# TXMIX-SE.net
KiCad netlist of a schematic drawn in Altium Designer
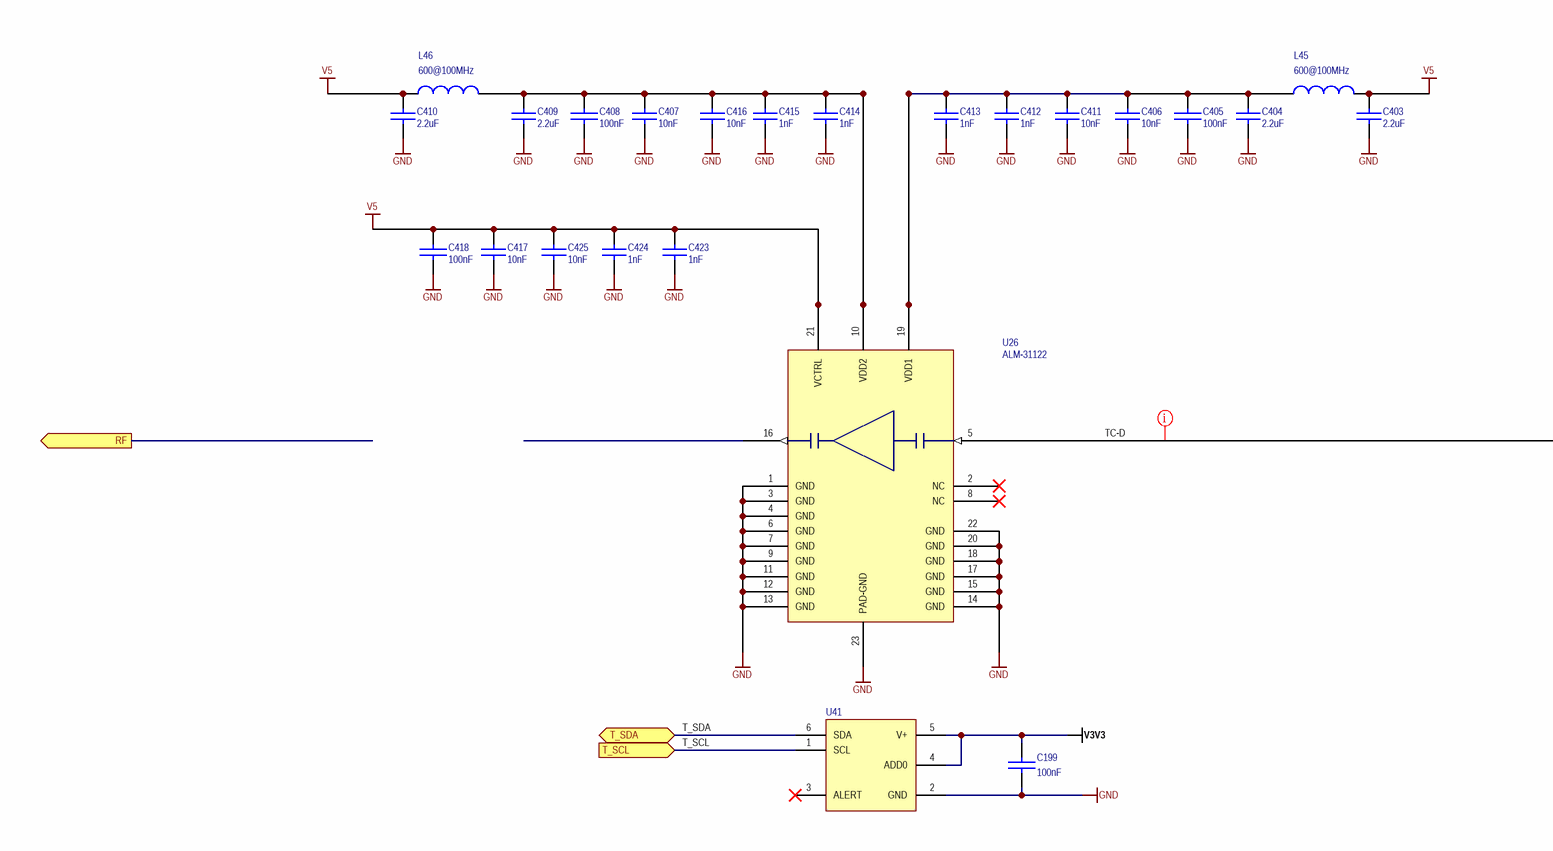
[diagram p0: TXMIX-SE.SchDoc, left]
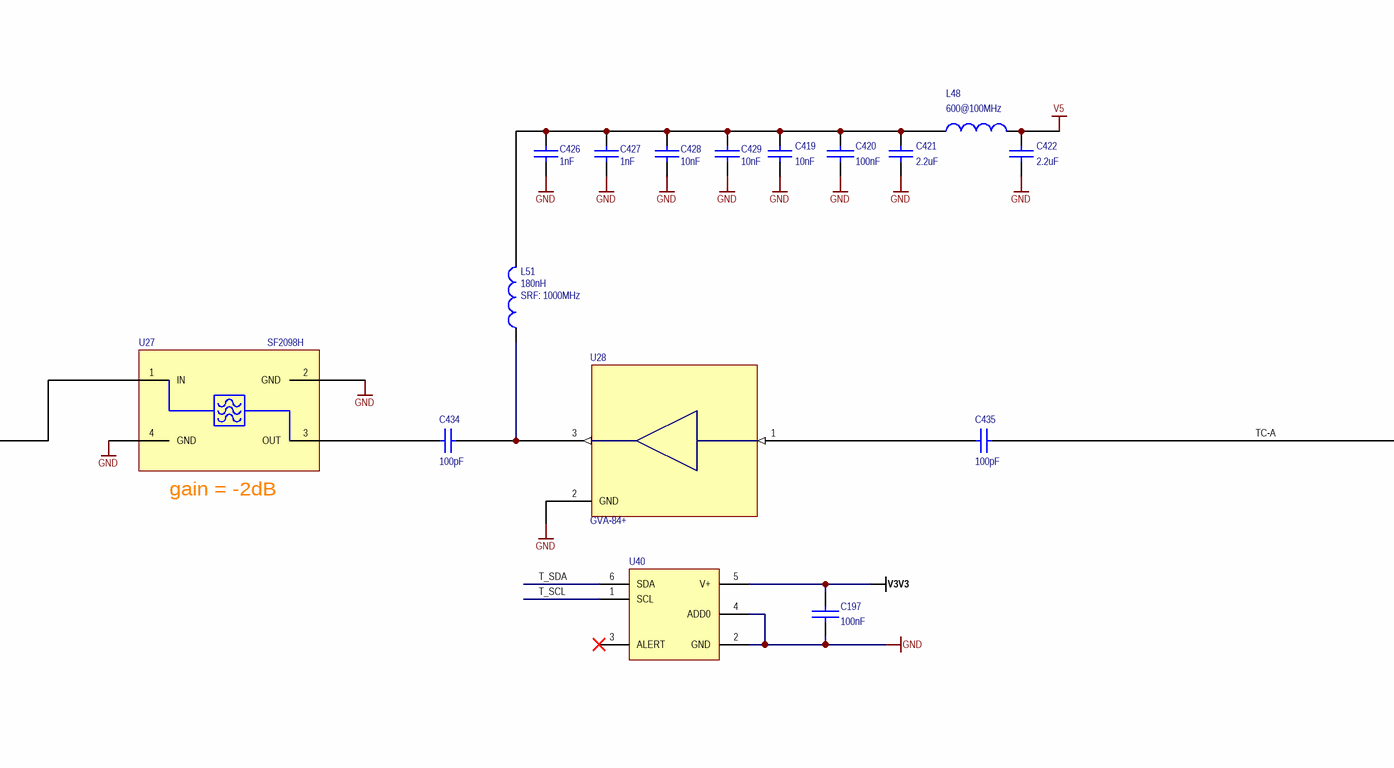
[diagram p1: TXMIX-SE.SchDoc, middle]
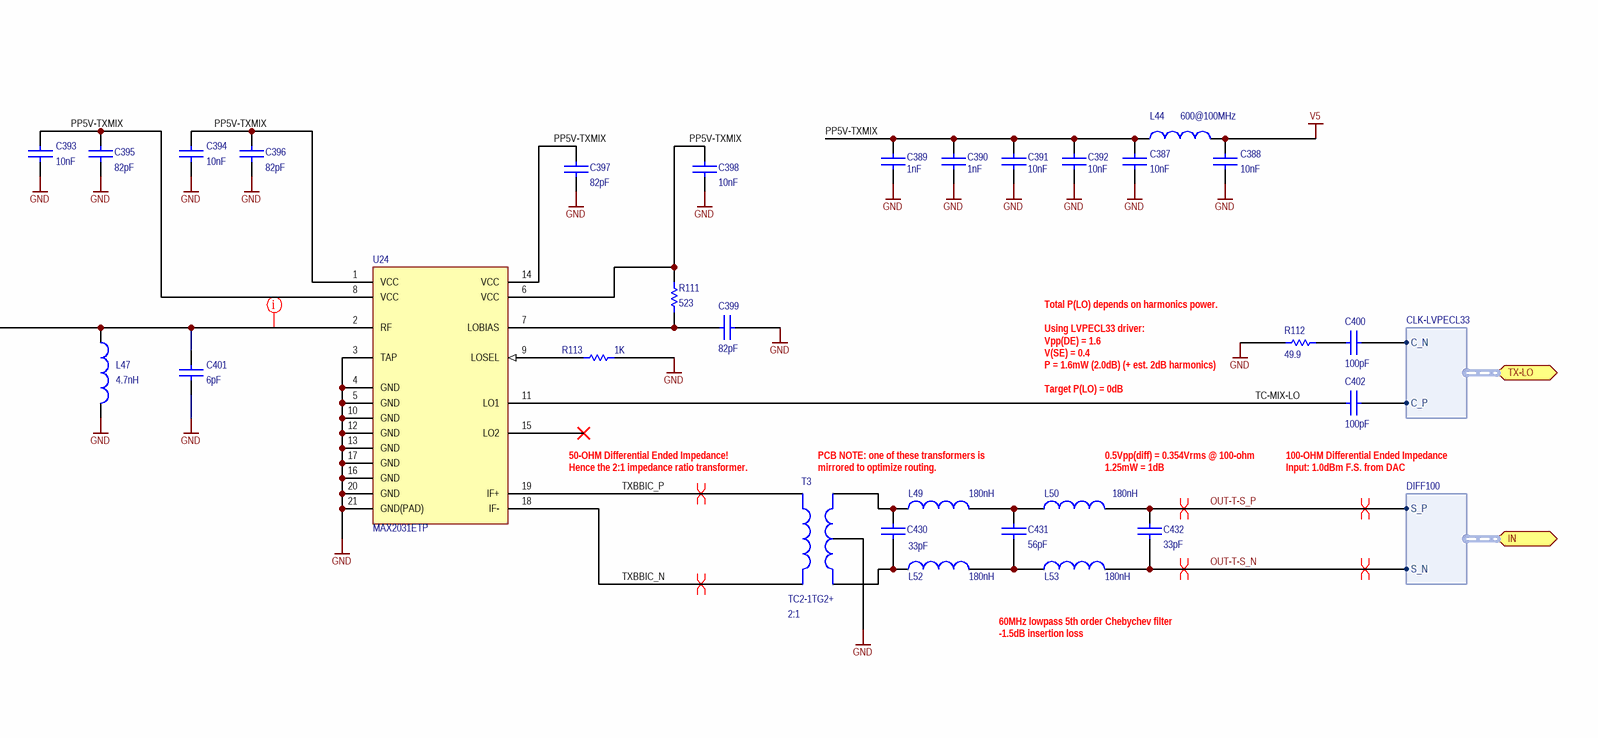
[diagram p2: TXMIX-SE.SchDoc, right]

(export (version "E")
  (design (tool "Eeschema 10.0.6"))
  (components
    (comp (ref "C197")
      (value "100nF")
      (footprint "CAPC100X50X55L25N")
      (description "Ceramic Capacitor 100nF ±10% 16V X7R 0402")
      (fields (field (name "MANUFACTURER") "Murata") (field (name "VOLTAGE") "16V"))
      (libsource (lib "*") (part "CAP"))
    )
    (comp (ref "C199")
      (value "100nF")
      (footprint "CAPC100X50X55L25N")
      (description "Ceramic Capacitor 100nF ±10% 16V X7R 0402")
      (fields (field (name "MANUFACTURER") "Murata") (field (name "VOLTAGE") "16V"))
      (libsource (lib "*") (part "CAP"))
    )
    (comp (ref "C387")
      (value "10nF")
      (footprint "CAPC100X50X55L25N")
      (description "Ceramic Capacitor 10nF ±10% 50V X7R 0402")
      (fields (field (name "VOLTAGE") "50V") (field (name "MANUFACTURER") "Murata"))
      (libsource (lib "Graviton") (part "CAP 0402"))
    )
    (comp (ref "C388")
      (value "10nF")
      (footprint "CAPC100X50X55L25N")
      (description "Ceramic Capacitor 10nF ±10% 50V X7R 0402")
      (fields (field (name "VOLTAGE") "50V") (field (name "MANUFACTURER") "Murata"))
      (libsource (lib "Graviton") (part "CAP 0402"))
    )
    (comp (ref "C389")
      (value "1nF")
      (footprint "CAPC100X50X55L25N")
      (description "Ceramic Capacitor 1nF ±10% 50V X7R 0402")
      (fields (field (name "VOLTAGE") "50V") (field (name "MANUFACTURER") "Murata"))
      (libsource (lib "Graviton") (part "CAP 0402"))
    )
    (comp (ref "C390")
      (value "1nF")
      (footprint "CAPC100X50X55L25N")
      (description "Ceramic Capacitor 1nF ±10% 50V X7R 0402")
      (fields (field (name "VOLTAGE") "50V") (field (name "MANUFACTURER") "Murata"))
      (libsource (lib "Graviton") (part "CAP 0402"))
    )
    (comp (ref "C391")
      (value "10nF")
      (footprint "CAPC100X50X55L25N")
      (description "Ceramic Capacitor 10nF ±10% 50V X7R 0402")
      (fields (field (name "VOLTAGE") "50V") (field (name "MANUFACTURER") "Murata"))
      (libsource (lib "Graviton") (part "CAP 0402"))
    )
    (comp (ref "C392")
      (value "10nF")
      (footprint "CAPC100X50X55L25N")
      (description "Ceramic Capacitor 10nF ±10% 50V X7R 0402")
      (fields (field (name "VOLTAGE") "50V") (field (name "MANUFACTURER") "Murata"))
      (libsource (lib "Graviton") (part "CAP 0402"))
    )
    (comp (ref "C393")
      (value "10nF")
      (footprint "CAPC100X50X55L25N")
      (description "Ceramic Capacitor 10nF ±10% 50V X7R 0402")
      (fields (field (name "VOLTAGE") "50V") (field (name "MANUFACTURER") "Murata"))
      (libsource (lib "Graviton") (part "CAP 0402"))
    )
    (comp (ref "C394")
      (value "10nF")
      (footprint "CAPC100X50X55L25N")
      (description "Ceramic Capacitor 10nF ±10% 50V X7R 0402")
      (fields (field (name "VOLTAGE") "50V") (field (name "MANUFACTURER") "Murata"))
      (libsource (lib "Graviton") (part "CAP 0402"))
    )
    (comp (ref "C395")
      (value "82pF")
      (footprint "CAPC100X50X55L25N")
      (description "Ceramic Capacitor 82pF ±5% 25V NP0 0402")
      (fields (field (name "VOLTAGE") "25V") (field (name "MANUFACTURER") "Vishay Vitramon"))
      (libsource (lib "generic") (part "CAP"))
    )
    (comp (ref "C396")
      (value "82pF")
      (footprint "CAPC100X50X55L25N")
      (description "Ceramic Capacitor 82pF ±5% 25V NP0 0402")
      (fields (field (name "MANUFACTURER") "Vishay Vitramon") (field (name "VOLTAGE") "25V"))
      (libsource (lib "generic") (part "CAP"))
    )
    (comp (ref "C397")
      (value "82pF")
      (footprint "CAPC100X50X55L25N")
      (description "Ceramic Capacitor 82pF ±5% 25V NP0 0402")
      (fields (field (name "VOLTAGE") "25V") (field (name "MANUFACTURER") "Vishay Vitramon"))
      (libsource (lib "generic") (part "CAP"))
    )
    (comp (ref "C398")
      (value "10nF")
      (footprint "CAPC100X50X55L25N")
      (description "Ceramic Capacitor 10nF ±10% 50V X7R 0402")
      (fields (field (name "VOLTAGE") "50V") (field (name "MANUFACTURER") "Murata"))
      (libsource (lib "Graviton") (part "CAP 0402"))
    )
    (comp (ref "C399")
      (value "82pF")
      (footprint "CAPC100X50X55L25N")
      (description "Ceramic Capacitor 82pF ±5% 25V NP0 0402")
      (fields (field (name "VOLTAGE") "25V") (field (name "MANUFACTURER") "Vishay Vitramon"))
      (libsource (lib "generic") (part "CAP"))
    )
    (comp (ref "C400")
      (value "100pF")
      (footprint "CAPC100X50X55L25N")
      (description "Ceramic Capacitor 100pF ±1% 25V NP0 0402")
      (fields (field (name "VOLTAGE") "25V") (field (name "MANUFACTURER") "Kemet"))
      (libsource (lib "generic") (part "CAP 0603"))
    )
    (comp (ref "C401")
      (value "6pF")
      (footprint "CAPC100X50X55L25N")
      (description "Ceramic Capacitor 6pF ±0.25pF 50V NP0 RF 0402")
      (fields (field (name "VOLTAGE") "50V") (field (name "MANUFACTURER") "Murata"))
      (libsource (lib "generic") (part "CAP 0402"))
    )
    (comp (ref "C402")
      (value "100pF")
      (footprint "CAPC100X50X55L25N")
      (description "Ceramic Capacitor 100pF ±1% 25V NP0 0402")
      (fields (field (name "VOLTAGE") "25V") (field (name "MANUFACTURER") "Kemet"))
      (libsource (lib "generic") (part "CAP 0603"))
    )
    (comp (ref "C403")
      (value "2.2uF")
      (footprint "generic:0805")
      (description "Ceramic Capacitor 2.2uF ±10% 10V X7R 0603")
      (fields (field (name "VOLTAGE") "10V") (field (name "MANUFACTURER") "Murata"))
      (libsource (lib "Graviton") (part "CAP 0805"))
    )
    (comp (ref "C404")
      (value "2.2uF")
      (footprint "generic:0805")
      (description "Ceramic Capacitor 2.2uF ±10% 10V X7R 0603")
      (fields (field (name "VOLTAGE") "10V") (field (name "MANUFACTURER") "Murata"))
      (libsource (lib "Graviton") (part "CAP 0805"))
    )
    (comp (ref "C405")
      (value "100nF")
      (footprint "CAPC100X50X55L25N")
      (description "Ceramic Capacitor 100nF ±10% 16V X7R 0402")
      (fields (field (name "MANUFACTURER") "Murata") (field (name "VOLTAGE") "16V"))
      (libsource (lib "*") (part "CAP"))
    )
    (comp (ref "C406")
      (value "10nF")
      (footprint "CAPC100X50X55L25N")
      (description "Ceramic Capacitor 10nF ±10% 50V X7R 0402")
      (fields (field (name "VOLTAGE") "50V") (field (name "MANUFACTURER") "Murata"))
      (libsource (lib "Graviton") (part "CAP 0402"))
    )
    (comp (ref "C407")
      (value "10nF")
      (footprint "CAPC100X50X55L25N")
      (description "Ceramic Capacitor 10nF ±10% 50V X7R 0402")
      (fields (field (name "VOLTAGE") "50V") (field (name "MANUFACTURER") "Murata"))
      (libsource (lib "Graviton") (part "CAP 0402"))
    )
    (comp (ref "C408")
      (value "100nF")
      (footprint "CAPC100X50X55L25N")
      (description "Ceramic Capacitor 100nF ±10% 16V X7R 0402")
      (fields (field (name "MANUFACTURER") "Murata") (field (name "VOLTAGE") "16V"))
      (libsource (lib "*") (part "CAP"))
    )
    (comp (ref "C409")
      (value "2.2uF")
      (footprint "generic:0805")
      (description "Ceramic Capacitor 2.2uF ±10% 10V X7R 0603")
      (fields (field (name "VOLTAGE") "10V") (field (name "MANUFACTURER") "Murata"))
      (libsource (lib "Graviton") (part "CAP 0805"))
    )
    (comp (ref "C410")
      (value "2.2uF")
      (footprint "generic:0805")
      (description "Ceramic Capacitor 2.2uF ±10% 10V X7R 0603")
      (fields (field (name "VOLTAGE") "10V") (field (name "MANUFACTURER") "Murata"))
      (libsource (lib "Graviton") (part "CAP 0805"))
    )
    (comp (ref "C411")
      (value "10nF")
      (footprint "CAPC100X50X55L25N")
      (description "Ceramic Capacitor 10nF ±10% 50V X7R 0402")
      (fields (field (name "VOLTAGE") "50V") (field (name "MANUFACTURER") "Murata"))
      (libsource (lib "Graviton") (part "CAP 0402"))
    )
    (comp (ref "C412")
      (value "1nF")
      (footprint "CAPC100X50X55L25N")
      (description "Ceramic Capacitor 1nF ±10% 50V X7R 0402")
      (fields (field (name "VOLTAGE") "50V") (field (name "MANUFACTURER") "Murata"))
      (libsource (lib "Graviton") (part "CAP 0402"))
    )
    (comp (ref "C413")
      (value "1nF")
      (footprint "CAPC100X50X55L25N")
      (description "Ceramic Capacitor 1nF ±10% 50V X7R 0402")
      (fields (field (name "VOLTAGE") "50V") (field (name "MANUFACTURER") "Murata"))
      (libsource (lib "Graviton") (part "CAP 0402"))
    )
    (comp (ref "C414")
      (value "1nF")
      (footprint "CAPC100X50X55L25N")
      (description "Ceramic Capacitor 1nF ±10% 50V X7R 0402")
      (fields (field (name "VOLTAGE") "50V") (field (name "MANUFACTURER") "Murata"))
      (libsource (lib "Graviton") (part "CAP 0402"))
    )
    (comp (ref "C415")
      (value "1nF")
      (footprint "CAPC100X50X55L25N")
      (description "Ceramic Capacitor 1nF ±10% 50V X7R 0402")
      (fields (field (name "VOLTAGE") "50V") (field (name "MANUFACTURER") "Murata"))
      (libsource (lib "Graviton") (part "CAP 0402"))
    )
    (comp (ref "C416")
      (value "10nF")
      (footprint "CAPC100X50X55L25N")
      (description "Ceramic Capacitor 10nF ±10% 50V X7R 0402")
      (fields (field (name "VOLTAGE") "50V") (field (name "MANUFACTURER") "Murata"))
      (libsource (lib "Graviton") (part "CAP 0402"))
    )
    (comp (ref "C417")
      (value "10nF")
      (footprint "CAPC100X50X55L25N")
      (description "Ceramic Capacitor 10nF ±10% 50V X7R 0402")
      (fields (field (name "VOLTAGE") "50V") (field (name "MANUFACTURER") "Murata"))
      (libsource (lib "Graviton") (part "CAP 0402"))
    )
    (comp (ref "C418")
      (value "100nF")
      (footprint "CAPC100X50X55L25N")
      (description "Ceramic Capacitor 100nF ±10% 16V X7R 0402")
      (fields (field (name "MANUFACTURER") "Murata") (field (name "VOLTAGE") "16V"))
      (libsource (lib "*") (part "CAP"))
    )
    (comp (ref "C419")
      (value "10nF")
      (footprint "CAPC100X50X55L25N")
      (description "Ceramic Capacitor 10nF ±10% 50V X7R 0402")
      (fields (field (name "VOLTAGE") "50V") (field (name "MANUFACTURER") "Murata"))
      (libsource (lib "Graviton") (part "CAP 0402"))
    )
    (comp (ref "C420")
      (value "100nF")
      (footprint "CAPC100X50X55L25N")
      (description "Ceramic Capacitor 100nF ±10% 16V X7R 0402")
      (fields (field (name "MANUFACTURER") "Murata") (field (name "VOLTAGE") "16V"))
      (libsource (lib "*") (part "CAP"))
    )
    (comp (ref "C421")
      (value "2.2uF")
      (footprint "generic:0805")
      (description "Ceramic Capacitor 2.2uF ±10% 10V X7R 0603")
      (fields (field (name "VOLTAGE") "10V") (field (name "MANUFACTURER") "Murata"))
      (libsource (lib "Graviton") (part "CAP 0805"))
    )
    (comp (ref "C422")
      (value "2.2uF")
      (footprint "generic:0805")
      (description "Ceramic Capacitor 2.2uF ±10% 10V X7R 0603")
      (fields (field (name "VOLTAGE") "10V") (field (name "MANUFACTURER") "Murata"))
      (libsource (lib "Graviton") (part "CAP 0805"))
    )
    (comp (ref "C423")
      (value "1nF")
      (footprint "CAPC100X50X55L25N")
      (description "Ceramic Capacitor 1nF ±10% 50V X7R 0402")
      (fields (field (name "VOLTAGE") "50V") (field (name "MANUFACTURER") "Murata"))
      (libsource (lib "Graviton") (part "CAP 0402"))
    )
    (comp (ref "C424")
      (value "1nF")
      (footprint "CAPC100X50X55L25N")
      (description "Ceramic Capacitor 1nF ±10% 50V X7R 0402")
      (fields (field (name "VOLTAGE") "50V") (field (name "MANUFACTURER") "Murata"))
      (libsource (lib "Graviton") (part "CAP 0402"))
    )
    (comp (ref "C425")
      (value "10nF")
      (footprint "CAPC100X50X55L25N")
      (description "Ceramic Capacitor 10nF ±10% 50V X7R 0402")
      (fields (field (name "VOLTAGE") "50V") (field (name "MANUFACTURER") "Murata"))
      (libsource (lib "Graviton") (part "CAP 0402"))
    )
    (comp (ref "C426")
      (value "1nF")
      (footprint "CAPC100X50X55L25N")
      (description "Ceramic Capacitor 1nF ±10% 50V X7R 0402")
      (fields (field (name "VOLTAGE") "50V") (field (name "MANUFACTURER") "Murata"))
      (libsource (lib "Graviton") (part "CAP 0402"))
    )
    (comp (ref "C427")
      (value "1nF")
      (footprint "CAPC100X50X55L25N")
      (description "Ceramic Capacitor 1nF ±10% 50V X7R 0402")
      (fields (field (name "VOLTAGE") "50V") (field (name "MANUFACTURER") "Murata"))
      (libsource (lib "Graviton") (part "CAP 0402"))
    )
    (comp (ref "C428")
      (value "10nF")
      (footprint "CAPC100X50X55L25N")
      (description "Ceramic Capacitor 10nF ±10% 50V X7R 0402")
      (fields (field (name "VOLTAGE") "50V") (field (name "MANUFACTURER") "Murata"))
      (libsource (lib "Graviton") (part "CAP 0402"))
    )
    (comp (ref "C429")
      (value "10nF")
      (footprint "CAPC100X50X55L25N")
      (description "Ceramic Capacitor 10nF ±10% 50V X7R 0402")
      (fields (field (name "VOLTAGE") "50V") (field (name "MANUFACTURER") "Murata"))
      (libsource (lib "Graviton") (part "CAP 0402"))
    )
    (comp (ref "C430")
      (value "33pF")
      (footprint "CAPC100X50X55L25N")
      (description "Ceramic Capacitor 33pF ±5% 50V NP0 0402")
      (fields (field (name "VOLTAGE") "50V") (field (name "MANUFACTURER") "Murata"))
      (libsource (lib "Graviton") (part "CAP 0402"))
    )
    (comp (ref "C431")
      (value "56pF")
      (footprint "CAPC100X50X55L25N")
      (description "Ceramic Capacitor 56pF ±5% 50V NP0 0402")
      (fields (field (name "VOLTAGE") "50V") (field (name "MANUFACTURER") "Murata"))
      (libsource (lib "Graviton") (part "CAP 0402"))
    )
    (comp (ref "C432")
      (value "33pF")
      (footprint "CAPC100X50X55L25N")
      (description "Ceramic Capacitor 33pF ±5% 50V NP0 0402")
      (fields (field (name "VOLTAGE") "50V") (field (name "MANUFACTURER") "Murata"))
      (libsource (lib "Graviton") (part "CAP 0402"))
    )
    (comp (ref "C434")
      (value "100pF")
      (footprint "CAPC100X50X55L25N")
      (description "Ceramic Capacitor 100pF ±1% 25V NP0 0402")
      (fields (field (name "MANUFACTURER") "Kemet") (field (name "VOLTAGE") "25V"))
      (libsource (lib "generic") (part "CAP 0603"))
    )
    (comp (ref "C435")
      (value "100pF")
      (footprint "CAPC100X50X55L25N")
      (description "Ceramic Capacitor 100pF ±1% 25V NP0 0402")
      (fields (field (name "VOLTAGE") "25V") (field (name "MANUFACTURER") "Kemet"))
      (libsource (lib "generic") (part "CAP 0603"))
    )
    (comp (ref "L44")
      (value "600@100MHz")
      (footprint "INDC1005X55N")
      (description "Ferrite Bead 600-Ohm @ 100MHz 900mA 0402")
      (fields (field (name "MANUFACTURER") "Murata") (field (name "TOLERANCE") "±25%"))
      (libsource (lib "") (part "IND 0402_1"))
    )
    (comp (ref "L45")
      (value "600@100MHz")
      (footprint "INDC1005X55N")
      (description "Ferrite Bead 600-Ohm @ 100MHz 900mA 0402")
      (fields (field (name "MANUFACTURER") "Murata") (field (name "TOLERANCE") "±25%"))
      (libsource (lib "Graviton") (part "IND 0402"))
    )
    (comp (ref "L46")
      (value "600@100MHz")
      (footprint "INDC1005X55N")
      (description "Ferrite Bead 600-Ohm @ 100MHz 900mA 0402")
      (fields (field (name "MANUFACTURER") "Murata") (field (name "TOLERANCE") "±25%"))
      (libsource (lib "Graviton") (part "IND 0402"))
    )
    (comp (ref "L47")
      (value "4.7nH")
      (footprint "0603")
      (description "Inductor Multilayer 4.7nH ±5% 0603")
      (fields (field (name "MANUFACTURER") "Murata") (field (name "TOLERANCE") "±0.3nH"))
      (libsource (lib "Graviton") (part "IND 0603"))
    )
    (comp (ref "L48")
      (value "600@100MHz")
      (footprint "INDC1005X55N")
      (description "Ferrite Bead 600-Ohm @ 100MHz 900mA 0402")
      (fields (field (name "MANUFACTURER") "Murata") (field (name "TOLERANCE") "±25%"))
      (libsource (lib "") (part "IND 0402_1"))
    )
    (comp (ref "L49")
      (value "180nH")
      (footprint "0603")
      (description "Inductor Wirewound 180nH ±2% 0603")
      (fields (field (name "MANUFACTURER") "Murata") (field (name "TOLERANCE") "±2%"))
      (libsource (lib "generic") (part "INDUCTOR"))
    )
    (comp (ref "L50")
      (value "180nH")
      (footprint "0603")
      (description "Inductor Wirewound 180nH ±2% 0603")
      (fields (field (name "MANUFACTURER") "Murata") (field (name "TOLERANCE") "±2%"))
      (libsource (lib "generic") (part "INDUCTOR"))
    )
    (comp (ref "L51")
      (value "180nH")
      (footprint "INDC1005X55N")
      (description "Wirewound Inductor 180nH 560mA 0402")
      (fields
        (field (name "MANUFACTURER") "Murata")
        (field (name "SRF") "1000MHz")
        (field (name "Comment") "LQW15CNR18J1ZD")
      )
      (libsource (lib "") (part "IND 0603_1"))
    )
    (comp (ref "L52")
      (value "180nH")
      (footprint "0603")
      (description "Inductor Wirewound 180nH ±2% 0603")
      (fields (field (name "MANUFACTURER") "Murata") (field (name "TOLERANCE") "±2%"))
      (libsource (lib "generic") (part "INDUCTOR"))
    )
    (comp (ref "L53")
      (value "180nH")
      (footprint "0603")
      (description "Inductor Wirewound 180nH ±2% 0603")
      (fields (field (name "MANUFACTURER") "Murata") (field (name "TOLERANCE") "±2%"))
      (libsource (lib "generic") (part "INDUCTOR"))
    )
    (comp (ref "R111")
      (value "523")
      (footprint "generic:0603")
      (description "Thick Film Resistor 523 ±1% 0603")
      (fields (field (name "MANUFACTURER") "Yageo") (field (name "TOLERANCE") "±1%"))
      (libsource (lib "generic") (part "RES 0603"))
    )
    (comp (ref "R112")
      (value "49.9")
      (footprint "generic:0603")
      (description "Thick Film Resistor 49.9 ±1% 0603")
      (fields (field (name "MANUFACTURER") "Panasonic") (field (name "TOLERANCE") "±1%"))
      (libsource (lib "generic") (part "RES 0603"))
    )
    (comp (ref "R113")
      (value "1K")
      (footprint "RESC1005X40N")
      (description "Thick Film Resistor 1k ±1% 0402")
      (fields (field (name "MANUFACTURER") "Yageo") (field (name "TOLERANCE") "±1%"))
      (libsource (lib "Graviton") (part "RES 0402"))
    )
    (comp (ref "T3")
      (value "2:1")
      (footprint "AT224-1A")
      (description "RF Transformer 0.4 to 500MHz SMD")
      (fields
        (field (name "MANUFACTURER P/N") "TC2-1TG2+")
        (field (name "MANUFACTURER") "Mini-Circuits")
        (field (name "Comment") "TC2-1TG2+")
      )
      (libsource (lib "phase4") (part "TC1-1TG2+"))
    )
    (comp (ref "U24")
      (value "MAX2031ETP")
      (footprint "QFN21P65_500X500X80L55X30T320N")
      (description "Upconversion/Downconversion Mixer")
      (fields (field (name "MANUFACTURER") "Maxim"))
      (libsource (lib "maxim") (part "MAX2031ETP"))
    )
    (comp (ref "U26")
      (value "ALM-31122")
      (footprint "ALM-31122")
      (description "1-watt High-Linearity Power Amplifier")
      (fields (field (name "MANUFACTURER") "Avago"))
      (libsource (lib "avago") (part "ALM-31122"))
    )
    (comp (ref "U27")
      (value "SF2098H")
      (footprint "rfm:SM2016-4")
      (description "915 MHz SAW Filter")
      (fields (field (name "MANUFACTURER") "RFM"))
      (libsource (lib "rfm") (part "SF2098H"))
    )
    (comp (ref "U28")
      (value "GVA-84+")
      (footprint "SOT89")
      (description "High Gain Monolithic Amplifier, DC-7GHz 24dB Gain")
      (fields (field (name "MANUFACTURER") "Mini-Circuits"))
      (libsource (lib "Mini-Circuits") (part "GVA-84+"))
    )
    (comp (ref "U40")
      (value "TMP116AIDRVT")
      (footprint "SON7P65_200X200X80L25X30T170X110N")
      (description "High-Accuracy Temperature Sensor")
      (fields (field (name "MANUFACTURER") "Texas Instruments"))
      (libsource (lib "ti") (part "TMP116AIDRV"))
    )
    (comp (ref "U41")
      (value "TMP116AIDRVT")
      (footprint "SON7P65_200X200X80L25X30T170X110N")
      (description "High-Accuracy Temperature Sensor")
      (fields (field (name "MANUFACTURER") "Texas Instruments"))
      (libsource (lib "ti") (part "TMP116AIDRV"))
    )
  )
  (nets
    (net (code "3") (name "/C_N") (class "Default")
      (node (ref "C400") (pin "2") (pinfunction "2_2") (pintype "passive"))
    )
    (net (code "4") (name "/C_P") (class "Default")
      (node (ref "C402") (pin "2") (pinfunction "2_2") (pintype "passive"))
    )
    (net (code "5") (name "/OUT-T-S_N") (class "Default")
      (node (ref "C432") (pin "1") (pinfunction "1_1") (pintype "passive"))
      (node (ref "L53") (pin "1") (pinfunction "1_1") (pintype "passive"))
    )
    (net (code "6") (name "/OUT-T-S_P") (class "Default")
      (node (ref "C432") (pin "2") (pinfunction "2_2") (pintype "passive"))
      (node (ref "L50") (pin "1") (pinfunction "1_1") (pintype "passive"))
    )
    (net (code "7") (name "/PP5V-TXMIX") (class "Default")
      (node (ref "C387") (pin "2") (pinfunction "2_2") (pintype "passive"))
      (node (ref "C389") (pin "2") (pinfunction "2_2") (pintype "passive"))
      (node (ref "C390") (pin "2") (pinfunction "2_2") (pintype "passive"))
      (node (ref "C391") (pin "2") (pinfunction "2_2") (pintype "passive"))
      (node (ref "C392") (pin "2") (pinfunction "2_2") (pintype "passive"))
      (node (ref "C393") (pin "2") (pinfunction "2_2") (pintype "passive"))
      (node (ref "C394") (pin "2") (pinfunction "2_2") (pintype "passive"))
      (node (ref "C395") (pin "2") (pinfunction "2_2") (pintype "passive"))
      (node (ref "C396") (pin "2") (pinfunction "2_2") (pintype "passive"))
      (node (ref "C397") (pin "2") (pinfunction "2_2") (pintype "passive"))
      (node (ref "C398") (pin "2") (pinfunction "2_2") (pintype "passive"))
      (node (ref "L44") (pin "2") (pinfunction "2_2") (pintype "passive"))
      (node (ref "R111") (pin "1") (pinfunction "1_1") (pintype "passive"))
      (node (ref "U24") (pin "1") (pinfunction "VCC_1") (pintype "power_in"))
      (node (ref "U24") (pin "14") (pinfunction "VCC_14") (pintype "power_in"))
      (node (ref "U24") (pin "6") (pinfunction "VCC_6") (pintype "power_in"))
      (node (ref "U24") (pin "8") (pinfunction "VCC_8") (pintype "power_in"))
    )
    (net (code "9") (name "/TC-A") (class "Default")
      (node (ref "C401") (pin "2") (pinfunction "2_2") (pintype "passive"))
      (node (ref "C435") (pin "2") (pinfunction "2_2") (pintype "passive"))
      (node (ref "L47") (pin "2") (pinfunction "2_2") (pintype "passive"))
      (node (ref "U24") (pin "2") (pinfunction "RF_2") (pintype "passive"))
    )
    (net (code "10") (name "/TC-D") (class "Default")
      (node (ref "U26") (pin "5") (pinfunction "RFIN_5") (pintype "input"))
      (node (ref "U27") (pin "1") (pinfunction "IN_1") (pintype "passive"))
    )
    (net (code "11") (name "/TC-MIX-LO") (class "Default")
      (node (ref "C402") (pin "1") (pinfunction "1_1") (pintype "passive"))
      (node (ref "U24") (pin "11") (pinfunction "LO1_11") (pintype "passive"))
    )
    (net (code "12") (name "/TXBBIC_N") (class "Default")
      (node (ref "T3") (pin "6") (pinfunction "Pri+_6") (pintype "passive"))
      (node (ref "U24") (pin "18") (pinfunction "IF-_18") (pintype "passive"))
    )
    (net (code "13") (name "/TXBBIC_P") (class "Default")
      (node (ref "T3") (pin "4") (pinfunction "Pri-_4") (pintype "passive"))
      (node (ref "U24") (pin "19") (pinfunction "IF+_19") (pintype "passive"))
    )
    (net (code "14") (name "/T_SCL") (class "Default")
      (node (ref "U40") (pin "1") (pinfunction "SCL_1") (pintype "passive"))
      (node (ref "U41") (pin "1") (pinfunction "SCL_1") (pintype "passive"))
    )
    (net (code "15") (name "/T_SDA") (class "Default")
      (node (ref "U40") (pin "6") (pinfunction "SDA_6") (pintype "passive"))
      (node (ref "U41") (pin "6") (pinfunction "SDA_6") (pintype "passive"))
    )
    (net (code "18") (name "GND") (class "Default")
      (node (ref "C197") (pin "1") (pinfunction "1_1") (pintype "passive"))
      (node (ref "C199") (pin "1") (pinfunction "1_1") (pintype "passive"))
      (node (ref "C387") (pin "1") (pinfunction "1_1") (pintype "passive"))
      (node (ref "C388") (pin "1") (pinfunction "1_1") (pintype "passive"))
      (node (ref "C389") (pin "1") (pinfunction "1_1") (pintype "passive"))
      (node (ref "C390") (pin "1") (pinfunction "1_1") (pintype "passive"))
      (node (ref "C391") (pin "1") (pinfunction "1_1") (pintype "passive"))
      (node (ref "C392") (pin "1") (pinfunction "1_1") (pintype "passive"))
      (node (ref "C393") (pin "1") (pinfunction "1_1") (pintype "passive"))
      (node (ref "C394") (pin "1") (pinfunction "1_1") (pintype "passive"))
      (node (ref "C395") (pin "1") (pinfunction "1_1") (pintype "passive"))
      (node (ref "C396") (pin "1") (pinfunction "1_1") (pintype "passive"))
      (node (ref "C397") (pin "1") (pinfunction "1_1") (pintype "passive"))
      (node (ref "C398") (pin "1") (pinfunction "1_1") (pintype "passive"))
      (node (ref "C399") (pin "2") (pinfunction "2_2") (pintype "passive"))
      (node (ref "C401") (pin "1") (pinfunction "1_1") (pintype "passive"))
      (node (ref "C403") (pin "1") (pinfunction "1_1") (pintype "passive"))
      (node (ref "C404") (pin "1") (pinfunction "1_1") (pintype "passive"))
      (node (ref "C405") (pin "1") (pinfunction "1_1") (pintype "passive"))
      (node (ref "C406") (pin "1") (pinfunction "1_1") (pintype "passive"))
      (node (ref "C407") (pin "1") (pinfunction "1_1") (pintype "passive"))
      (node (ref "C408") (pin "1") (pinfunction "1_1") (pintype "passive"))
      (node (ref "C409") (pin "1") (pinfunction "1_1") (pintype "passive"))
      (node (ref "C410") (pin "1") (pinfunction "1_1") (pintype "passive"))
      (node (ref "C411") (pin "2") (pinfunction "2_2") (pintype "passive"))
      (node (ref "C412") (pin "2") (pinfunction "2_2") (pintype "passive"))
      (node (ref "C413") (pin "2") (pinfunction "2_2") (pintype "passive"))
      (node (ref "C414") (pin "2") (pinfunction "2_2") (pintype "passive"))
      (node (ref "C415") (pin "2") (pinfunction "2_2") (pintype "passive"))
      (node (ref "C416") (pin "2") (pinfunction "2_2") (pintype "passive"))
      (node (ref "C417") (pin "1") (pinfunction "1_1") (pintype "passive"))
      (node (ref "C418") (pin "1") (pinfunction "1_1") (pintype "passive"))
      (node (ref "C419") (pin "1") (pinfunction "1_1") (pintype "passive"))
      (node (ref "C420") (pin "1") (pinfunction "1_1") (pintype "passive"))
      (node (ref "C421") (pin "1") (pinfunction "1_1") (pintype "passive"))
      (node (ref "C422") (pin "1") (pinfunction "1_1") (pintype "passive"))
      (node (ref "C423") (pin "2") (pinfunction "2_2") (pintype "passive"))
      (node (ref "C424") (pin "2") (pinfunction "2_2") (pintype "passive"))
      (node (ref "C425") (pin "2") (pinfunction "2_2") (pintype "passive"))
      (node (ref "C426") (pin "1") (pinfunction "1_1") (pintype "passive"))
      (node (ref "C427") (pin "1") (pinfunction "1_1") (pintype "passive"))
      (node (ref "C428") (pin "1") (pinfunction "1_1") (pintype "passive"))
      (node (ref "C429") (pin "1") (pinfunction "1_1") (pintype "passive"))
      (node (ref "L47") (pin "1") (pinfunction "1_1") (pintype "passive"))
      (node (ref "R112") (pin "1") (pinfunction "1_1") (pintype "passive"))
      (node (ref "R113") (pin "2") (pinfunction "2_2") (pintype "passive"))
      (node (ref "T3") (pin "2") (pinfunction "SecCT_2") (pintype "passive"))
      (node (ref "U24") (pin "10") (pinfunction "GND_10") (pintype "power_in"))
      (node (ref "U24") (pin "12") (pinfunction "GND_12") (pintype "power_in"))
      (node (ref "U24") (pin "13") (pinfunction "GND_13") (pintype "power_in"))
      (node (ref "U24") (pin "16") (pinfunction "GND_16") (pintype "power_in"))
      (node (ref "U24") (pin "17") (pinfunction "GND_17") (pintype "power_in"))
      (node (ref "U24") (pin "20") (pinfunction "GND_20") (pintype "power_in"))
      (node (ref "U24") (pin "21") (pinfunction "GND(PAD)_21") (pintype "power_in"))
      (node (ref "U24") (pin "3") (pinfunction "TAP_3") (pintype "passive"))
      (node (ref "U24") (pin "4") (pinfunction "GND_4") (pintype "power_in"))
      (node (ref "U24") (pin "5") (pinfunction "GND_5") (pintype "power_in"))
      (node (ref "U26") (pin "1") (pinfunction "GND_1") (pintype "passive"))
      (node (ref "U26") (pin "11") (pinfunction "GND_11") (pintype "passive"))
      (node (ref "U26") (pin "12") (pinfunction "GND_12") (pintype "passive"))
      (node (ref "U26") (pin "13") (pinfunction "GND_13") (pintype "passive"))
      (node (ref "U26") (pin "14") (pinfunction "GND_14") (pintype "passive"))
      (node (ref "U26") (pin "15") (pinfunction "GND_15") (pintype "passive"))
      (node (ref "U26") (pin "17") (pinfunction "GND_17") (pintype "passive"))
      (node (ref "U26") (pin "18") (pinfunction "GND_18") (pintype "passive"))
      (node (ref "U26") (pin "20") (pinfunction "GND_20") (pintype "passive"))
      (node (ref "U26") (pin "22") (pinfunction "GND_22") (pintype "passive"))
      (node (ref "U26") (pin "23") (pinfunction "PAD-GND_23") (pintype "passive"))
      (node (ref "U26") (pin "3") (pinfunction "GND_3") (pintype "passive"))
      (node (ref "U26") (pin "4") (pinfunction "GND_4") (pintype "passive"))
      (node (ref "U26") (pin "6") (pinfunction "GND_6") (pintype "passive"))
      (node (ref "U26") (pin "7") (pinfunction "GND_7") (pintype "passive"))
      (node (ref "U26") (pin "9") (pinfunction "GND_9") (pintype "passive"))
      (node (ref "U27") (pin "2") (pinfunction "GND_2") (pintype "passive"))
      (node (ref "U27") (pin "4") (pinfunction "GND_4") (pintype "passive"))
      (node (ref "U28") (pin "2") (pinfunction "GND_2") (pintype "passive"))
      (node (ref "U40") (pin "2") (pinfunction "GND_2") (pintype "passive"))
      (node (ref "U40") (pin "4") (pinfunction "ADD0_4") (pintype "passive"))
      (node (ref "U41") (pin "2") (pinfunction "GND_2") (pintype "passive"))
    )
    (net (code "19") (name "Net-(C400-Pad1)") (class "Default")
      (node (ref "C400") (pin "1") (pinfunction "1_1") (pintype "passive"))
      (node (ref "R112") (pin "2") (pinfunction "2_2") (pintype "passive"))
    )
    (net (code "20") (name "Net-(C419-Pad2)") (class "Default")
      (node (ref "C419") (pin "2") (pinfunction "2_2") (pintype "passive"))
      (node (ref "C420") (pin "2") (pinfunction "2_2") (pintype "passive"))
      (node (ref "C421") (pin "2") (pinfunction "2_2") (pintype "passive"))
      (node (ref "C426") (pin "2") (pinfunction "2_2") (pintype "passive"))
      (node (ref "C427") (pin "2") (pinfunction "2_2") (pintype "passive"))
      (node (ref "C428") (pin "2") (pinfunction "2_2") (pintype "passive"))
      (node (ref "C429") (pin "2") (pinfunction "2_2") (pintype "passive"))
      (node (ref "L48") (pin "2") (pinfunction "2_2") (pintype "passive"))
      (node (ref "L51") (pin "2") (pinfunction "2_2") (pintype "passive"))
    )
    (net (code "21") (name "Net-(C431-Pad1)") (class "Default")
      (node (ref "C431") (pin "1") (pinfunction "1_1") (pintype "passive"))
      (node (ref "L52") (pin "1") (pinfunction "1_1") (pintype "passive"))
      (node (ref "L53") (pin "2") (pinfunction "2_2") (pintype "passive"))
    )
    (net (code "22") (name "Net-(C431-Pad2)") (class "Default")
      (node (ref "C431") (pin "2") (pinfunction "2_2") (pintype "passive"))
      (node (ref "L49") (pin "1") (pinfunction "1_1") (pintype "passive"))
      (node (ref "L50") (pin "2") (pinfunction "2_2") (pintype "passive"))
    )
    (net (code "23") (name "Net-(T3-Sec+)") (class "Default")
      (node (ref "C430") (pin "1") (pinfunction "1_1") (pintype "passive"))
      (node (ref "L52") (pin "2") (pinfunction "2_2") (pintype "passive"))
      (node (ref "T3") (pin "1") (pinfunction "Sec+_1") (pintype "passive"))
    )
    (net (code "24") (name "Net-(T3-Sec-)") (class "Default")
      (node (ref "C430") (pin "2") (pinfunction "2_2") (pintype "passive"))
      (node (ref "L49") (pin "2") (pinfunction "2_2") (pintype "passive"))
      (node (ref "T3") (pin "3") (pinfunction "Sec-_3") (pintype "passive"))
    )
    (net (code "25") (name "Net-(U24-LOBIAS)") (class "Default")
      (node (ref "C399") (pin "1") (pinfunction "1_1") (pintype "passive"))
      (node (ref "R111") (pin "2") (pinfunction "2_2") (pintype "passive"))
      (node (ref "U24") (pin "7") (pinfunction "LOBIAS_7") (pintype "passive"))
    )
    (net (code "26") (name "Net-(U24-LOSEL)") (class "Default")
      (node (ref "R113") (pin "1") (pinfunction "1_1") (pintype "passive"))
      (node (ref "U24") (pin "9") (pinfunction "LOSEL_9") (pintype "input"))
    )
    (net (code "27") (name "Net-(U26-VDD1)") (class "Default")
      (node (ref "C404") (pin "2") (pinfunction "2_2") (pintype "passive"))
      (node (ref "C405") (pin "2") (pinfunction "2_2") (pintype "passive"))
      (node (ref "C406") (pin "2") (pinfunction "2_2") (pintype "passive"))
      (node (ref "C411") (pin "1") (pinfunction "1_1") (pintype "passive"))
      (node (ref "C412") (pin "1") (pinfunction "1_1") (pintype "passive"))
      (node (ref "C413") (pin "1") (pinfunction "1_1") (pintype "passive"))
      (node (ref "L45") (pin "1") (pinfunction "1_1") (pintype "passive"))
      (node (ref "U26") (pin "19") (pinfunction "VDD1_19") (pintype "passive"))
    )
    (net (code "28") (name "Net-(U26-VDD2)") (class "Default")
      (node (ref "C407") (pin "2") (pinfunction "2_2") (pintype "passive"))
      (node (ref "C408") (pin "2") (pinfunction "2_2") (pintype "passive"))
      (node (ref "C409") (pin "2") (pinfunction "2_2") (pintype "passive"))
      (node (ref "C414") (pin "1") (pinfunction "1_1") (pintype "passive"))
      (node (ref "C415") (pin "1") (pinfunction "1_1") (pintype "passive"))
      (node (ref "C416") (pin "1") (pinfunction "1_1") (pintype "passive"))
      (node (ref "L46") (pin "2") (pinfunction "2_2") (pintype "passive"))
      (node (ref "U26") (pin "10") (pinfunction "VDD2_10") (pintype "passive"))
    )
    (net (code "29") (name "Net-(U27-OUT)") (class "Default")
      (node (ref "C434") (pin "1") (pinfunction "1_1") (pintype "passive"))
      (node (ref "U27") (pin "3") (pinfunction "OUT_3") (pintype "passive"))
    )
    (net (code "30") (name "Net-(U28-RFIN)") (class "Default")
      (node (ref "C435") (pin "1") (pinfunction "1_1") (pintype "passive"))
      (node (ref "U28") (pin "1") (pinfunction "RFIN_1") (pintype "input"))
    )
    (net (code "31") (name "Net-(U28-RFOUT)") (class "Default")
      (node (ref "C434") (pin "2") (pinfunction "2_2") (pintype "passive"))
      (node (ref "L51") (pin "1") (pinfunction "1_1") (pintype "passive"))
      (node (ref "U28") (pin "3") (pinfunction "RFOUT_3") (pintype "output"))
    )
    (net (code "32") (name "V3V3") (class "Default")
      (node (ref "C197") (pin "2") (pinfunction "2_2") (pintype "passive"))
      (node (ref "C199") (pin "2") (pinfunction "2_2") (pintype "passive"))
      (node (ref "U40") (pin "5") (pinfunction "V+_5") (pintype "passive"))
      (node (ref "U41") (pin "4") (pinfunction "ADD0_4") (pintype "passive"))
      (node (ref "U41") (pin "5") (pinfunction "V+_5") (pintype "passive"))
    )
    (net (code "33") (name "V5") (class "Default")
      (node (ref "C388") (pin "2") (pinfunction "2_2") (pintype "passive"))
      (node (ref "C403") (pin "2") (pinfunction "2_2") (pintype "passive"))
      (node (ref "C410") (pin "2") (pinfunction "2_2") (pintype "passive"))
      (node (ref "C417") (pin "2") (pinfunction "2_2") (pintype "passive"))
      (node (ref "C418") (pin "2") (pinfunction "2_2") (pintype "passive"))
      (node (ref "C422") (pin "2") (pinfunction "2_2") (pintype "passive"))
      (node (ref "C423") (pin "1") (pinfunction "1_1") (pintype "passive"))
      (node (ref "C424") (pin "1") (pinfunction "1_1") (pintype "passive"))
      (node (ref "C425") (pin "1") (pinfunction "1_1") (pintype "passive"))
      (node (ref "L44") (pin "1") (pinfunction "1_1") (pintype "passive"))
      (node (ref "L45") (pin "2") (pinfunction "2_2") (pintype "passive"))
      (node (ref "L46") (pin "1") (pinfunction "1_1") (pintype "passive"))
      (node (ref "L48") (pin "1") (pinfunction "1_1") (pintype "passive"))
      (node (ref "U26") (pin "21") (pinfunction "VCTRL_21") (pintype "passive"))
    )
    (net (code "34") (name "unconnected-(U24-LO2-Pad15)") (class "Default")
      (node (ref "U24") (pin "15") (pinfunction "LO2_15") (pintype "passive+no_connect"))
    )
    (net (code "35") (name "unconnected-(U26-NC-Pad2)") (class "Default")
      (node (ref "U26") (pin "2") (pinfunction "NC_2") (pintype "passive+no_connect"))
    )
    (net (code "36") (name "unconnected-(U26-NC-Pad8)") (class "Default")
      (node (ref "U26") (pin "8") (pinfunction "NC_8") (pintype "passive+no_connect"))
    )
    (net (code "37") (name "unconnected-(U26-RFOUT-Pad16)") (class "Default")
      (node (ref "U26") (pin "16") (pinfunction "RFOUT_16") (pintype "output"))
    )
    (net (code "38") (name "unconnected-(U40-ALERT-Pad3)") (class "Default")
      (node (ref "U40") (pin "3") (pinfunction "ALERT_3") (pintype "passive+no_connect"))
    )
    (net (code "39") (name "unconnected-(U41-ALERT-Pad3)") (class "Default")
      (node (ref "U41") (pin "3") (pinfunction "ALERT_3") (pintype "passive+no_connect"))
    )
  )
)
